# Trainii.net
KiCad netlist of a schematic drawn in EAGLE
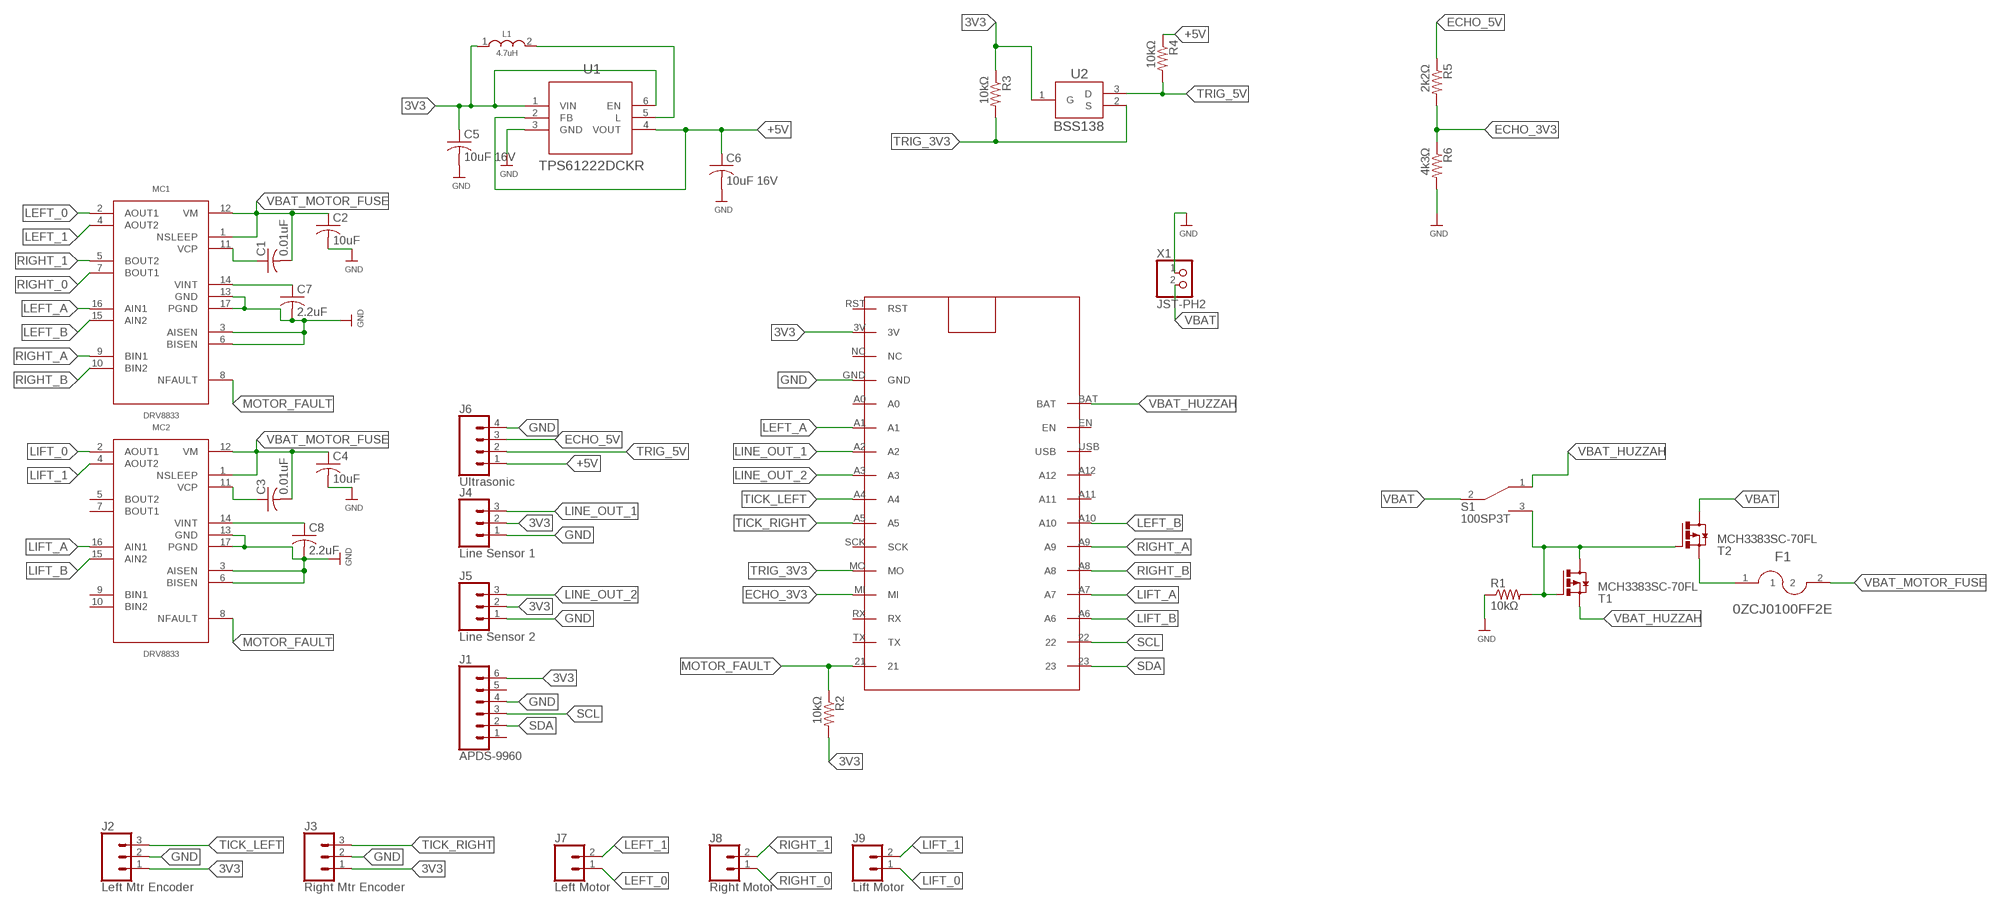
[diagram p0: schematic, sheet 1]

(export (version "E")
  (design (tool "Eeschema 10.0.6"))
  (components
    (comp (ref "C1")
      (value "0.01uF")
      (footprint "eagle-import:C0805")
      (libsource (lib "eagle-import") (part "C-USC0805"))
    )
    (comp (ref "C2")
      (value "10uF")
      (footprint "eagle-import:C0805")
      (libsource (lib "eagle-import") (part "C-USC0805"))
    )
    (comp (ref "C3")
      (value "0.01uF")
      (footprint "eagle-import:C0805")
      (libsource (lib "eagle-import") (part "C-USC0805"))
    )
    (comp (ref "C4")
      (value "10uF")
      (footprint "eagle-import:C0805")
      (libsource (lib "eagle-import") (part "C-USC0805"))
    )
    (comp (ref "C5")
      (value "10uF 16V")
      (footprint "eagle-import:C0805")
      (libsource (lib "eagle-import") (part "C-USC0805"))
    )
    (comp (ref "C6")
      (value "10uF 16V")
      (footprint "eagle-import:C0805")
      (libsource (lib "eagle-import") (part "C-USC0805"))
    )
    (comp (ref "C7")
      (value "2.2uF")
      (footprint "eagle-import:C0805")
      (libsource (lib "eagle-import") (part "C-USC0805"))
    )
    (comp (ref "C8")
      (value "2.2uF")
      (footprint "eagle-import:C0805")
      (libsource (lib "eagle-import") (part "C-USC0805"))
    )
    (comp (ref "F1")
      (value "0ZCJ0100FF2E")
      (footprint "eagle-import:1206")
      (libsource (lib "eagle-import") (part "0ZCJ0100FF2E"))
    )
    (comp (ref "J1")
      (value "APDS-9960")
      (footprint "eagle-import:1X06")
      (libsource (lib "eagle-import") (part "CONN_06SILK_FEMALE_PTH"))
    )
    (comp (ref "J2")
      (value "Left Mtr Encoder")
      (footprint "eagle-import:1X03")
      (libsource (lib "eagle-import") (part "CONN_03"))
    )
    (comp (ref "J3")
      (value "Right Mtr Encoder")
      (footprint "eagle-import:1X03")
      (libsource (lib "eagle-import") (part "CONN_03"))
    )
    (comp (ref "J4")
      (value "Line Sensor 1")
      (footprint "eagle-import:1X03")
      (libsource (lib "eagle-import") (part "CONN_03"))
    )
    (comp (ref "J5")
      (value "Line Sensor 2")
      (footprint "eagle-import:1X03")
      (libsource (lib "eagle-import") (part "CONN_03"))
    )
    (comp (ref "J6")
      (value "Ultrasonic")
      (footprint "eagle-import:1X04")
      (libsource (lib "eagle-import") (part "CONN_04"))
    )
    (comp (ref "J7")
      (value "Left Motor")
      (footprint "eagle-import:1X02")
      (libsource (lib "eagle-import") (part "CONN_02"))
    )
    (comp (ref "J8")
      (value "Right Motor")
      (footprint "eagle-import:1X02")
      (libsource (lib "eagle-import") (part "CONN_02"))
    )
    (comp (ref "J9")
      (value "Lift Motor")
      (footprint "eagle-import:1X02")
      (libsource (lib "eagle-import") (part "CONN_02"))
    )
    (comp (ref "L1")
      (value "4.7uH")
      (footprint "eagle-import:VLS3012HBX")
      (libsource (lib "eagle-import") (part "VLS3012HBX"))
    )
    (comp (ref "M1")
      (value "ESP32")
      (footprint "eagle-import:ESP32")
      (libsource (lib "eagle-import") (part "ESP32"))
    )
    (comp (ref "MC1")
      (value "DRV8833")
      (footprint "eagle-import:HTSSOP-16")
      (libsource (lib "eagle-import") (part "DRV8833"))
    )
    (comp (ref "MC2")
      (value "DRV8833")
      (footprint "eagle-import:HTSSOP-16")
      (libsource (lib "eagle-import") (part "DRV8833"))
    )
    (comp (ref "R1")
      (value "10kΩ")
      (footprint "eagle-import:R0805")
      (libsource (lib "eagle-import") (part "R-US_R0805"))
    )
    (comp (ref "R2")
      (value "10kΩ")
      (footprint "eagle-import:R0805")
      (libsource (lib "eagle-import") (part "R-US_R0805"))
    )
    (comp (ref "R3")
      (value "10kΩ")
      (footprint "eagle-import:R0805")
      (libsource (lib "eagle-import") (part "R-US_R0805"))
    )
    (comp (ref "R4")
      (value "10kΩ")
      (footprint "eagle-import:R0805")
      (libsource (lib "eagle-import") (part "R-US_R0805"))
    )
    (comp (ref "R5")
      (value "2k2Ω")
      (footprint "eagle-import:M0805")
      (libsource (lib "eagle-import") (part "R-US_M0805"))
    )
    (comp (ref "R6")
      (value "4k3Ω")
      (footprint "eagle-import:M0805")
      (libsource (lib "eagle-import") (part "R-US_M0805"))
    )
    (comp (ref "S1")
      (value "100SP3T")
      (footprint "eagle-import:100SP3T")
      (libsource (lib "eagle-import") (part "100SP3T"))
    )
    (comp (ref "T1")
      (value "MCH3383SC-70FL")
      (footprint "eagle-import:SOTFL65P210X90-3")
      (libsource (lib "eagle-import") (part "MCH3383SC-70FL"))
    )
    (comp (ref "T2")
      (value "MCH3383SC-70FL")
      (footprint "eagle-import:SOTFL65P210X90-3")
      (libsource (lib "eagle-import") (part "MCH3383SC-70FL"))
    )
    (comp (ref "U1")
      (value "TPS61222DCKR")
      (footprint "eagle-import:DCK6")
      (libsource (lib "eagle-import") (part "TPS61222DCKR"))
    )
    (comp (ref "U2")
      (value "BSS138")
      (footprint "eagle-import:SOT-23-3L")
      (libsource (lib "eagle-import") (part "BSS138"))
    )
    (comp (ref "X1")
      (value "JST-PH2")
      (footprint "eagle-import:JST-PH")
      (libsource (lib "eagle-import") (part "JST-PH2"))
    )
  )
  (nets
    (net (code "1") (name "+5V") (class "Default")
      (node (ref "C6") (pin "1") (pinfunction "1_1") (pintype "passive"))
      (node (ref "J6") (pin "1") (pinfunction "1_1") (pintype "passive"))
      (node (ref "R4") (pin "1") (pinfunction "1_1") (pintype "passive"))
      (node (ref "U1") (pin "2") (pinfunction "FB_2") (pintype "input"))
      (node (ref "U1") (pin "4") (pinfunction "VOUT_4") (pintype "output"))
    )
    (net (code "2") (name "3V3") (class "Default")
      (node (ref "C5") (pin "1") (pinfunction "1_1") (pintype "passive"))
      (node (ref "J1") (pin "6") (pinfunction "6_6") (pintype "passive"))
      (node (ref "J2") (pin "1") (pinfunction "1_1") (pintype "passive"))
      (node (ref "J3") (pin "1") (pinfunction "1_1") (pintype "passive"))
      (node (ref "J4") (pin "2") (pinfunction "2_2") (pintype "passive"))
      (node (ref "J5") (pin "2") (pinfunction "2_2") (pintype "passive"))
      (node (ref "L1") (pin "1") (pinfunction "IN_1") (pintype "passive"))
      (node (ref "M1") (pin "3V") (pinfunction "3V_3V") (pintype "bidirectional"))
      (node (ref "R2") (pin "2") (pinfunction "2_2") (pintype "passive"))
      (node (ref "R3") (pin "1") (pinfunction "1_1") (pintype "passive"))
      (node (ref "U1") (pin "1") (pinfunction "VIN_1") (pintype "input"))
      (node (ref "U1") (pin "6") (pinfunction "EN_6") (pintype "input"))
      (node (ref "U2") (pin "1") (pinfunction "G_1") (pintype "passive"))
    )
    (net (code "3") (name "ECHO_3V3") (class "Default")
      (node (ref "M1") (pin "MI") (pinfunction "MI_MI") (pintype "bidirectional"))
      (node (ref "R5") (pin "2") (pinfunction "2_2") (pintype "passive"))
      (node (ref "R6") (pin "1") (pinfunction "1_1") (pintype "passive"))
    )
    (net (code "4") (name "ECHO_5V") (class "Default")
      (node (ref "J6") (pin "3") (pinfunction "3_3") (pintype "passive"))
      (node (ref "R5") (pin "1") (pinfunction "1_1") (pintype "passive"))
    )
    (net (code "5") (name "GND") (class "Default")
      (node (ref "C2") (pin "2") (pinfunction "2_2") (pintype "passive"))
      (node (ref "C4") (pin "2") (pinfunction "2_2") (pintype "passive"))
      (node (ref "C5") (pin "2") (pinfunction "2_2") (pintype "passive"))
      (node (ref "C6") (pin "2") (pinfunction "2_2") (pintype "passive"))
      (node (ref "C7") (pin "2") (pinfunction "2_2") (pintype "passive"))
      (node (ref "C8") (pin "2") (pinfunction "2_2") (pintype "passive"))
      (node (ref "J1") (pin "4") (pinfunction "4_4") (pintype "passive"))
      (node (ref "J2") (pin "2") (pinfunction "2_2") (pintype "passive"))
      (node (ref "J3") (pin "2") (pinfunction "2_2") (pintype "passive"))
      (node (ref "J4") (pin "1") (pinfunction "1_1") (pintype "passive"))
      (node (ref "J5") (pin "1") (pinfunction "1_1") (pintype "passive"))
      (node (ref "J6") (pin "4") (pinfunction "4_4") (pintype "passive"))
      (node (ref "M1") (pin "GND") (pinfunction "GND_GND") (pintype "bidirectional"))
      (node (ref "MC1") (pin "13") (pinfunction "GND_13") (pintype "power_in"))
      (node (ref "MC1") (pin "17") (pinfunction "PGND_17") (pintype "power_in"))
      (node (ref "MC1") (pin "3") (pinfunction "AISEN_3") (pintype "bidirectional"))
      (node (ref "MC1") (pin "6") (pinfunction "BISEN_6") (pintype "bidirectional"))
      (node (ref "MC2") (pin "13") (pinfunction "GND_13") (pintype "power_in"))
      (node (ref "MC2") (pin "17") (pinfunction "PGND_17") (pintype "power_in"))
      (node (ref "MC2") (pin "3") (pinfunction "AISEN_3") (pintype "bidirectional"))
      (node (ref "MC2") (pin "6") (pinfunction "BISEN_6") (pintype "bidirectional"))
      (node (ref "R1") (pin "1") (pinfunction "1_1") (pintype "passive"))
      (node (ref "R6") (pin "2") (pinfunction "2_2") (pintype "passive"))
      (node (ref "U1") (pin "3") (pinfunction "GND_3") (pintype "power_in"))
      (node (ref "X1") (pin "1") (pinfunction "1_1") (pintype "passive"))
    )
    (net (code "6") (name "LEFT_0") (class "Default")
      (node (ref "J7") (pin "1") (pinfunction "1_1") (pintype "passive"))
      (node (ref "MC1") (pin "2") (pinfunction "AOUT1_2") (pintype "output"))
    )
    (net (code "7") (name "LEFT_1") (class "Default")
      (node (ref "J7") (pin "2") (pinfunction "2_2") (pintype "passive"))
      (node (ref "MC1") (pin "4") (pinfunction "AOUT2_4") (pintype "output"))
    )
    (net (code "8") (name "LEFT_A") (class "Default")
      (node (ref "M1") (pin "A1") (pinfunction "A1_A1") (pintype "bidirectional"))
      (node (ref "MC1") (pin "16") (pinfunction "AIN1_16") (pintype "input"))
    )
    (net (code "9") (name "LEFT_B") (class "Default")
      (node (ref "M1") (pin "A10") (pinfunction "A10_A10") (pintype "bidirectional"))
      (node (ref "MC1") (pin "15") (pinfunction "AIN2_15") (pintype "input"))
    )
    (net (code "10") (name "LIFT_0") (class "Default")
      (node (ref "J9") (pin "1") (pinfunction "1_1") (pintype "passive"))
      (node (ref "MC2") (pin "2") (pinfunction "AOUT1_2") (pintype "output"))
    )
    (net (code "11") (name "LIFT_1") (class "Default")
      (node (ref "J9") (pin "2") (pinfunction "2_2") (pintype "passive"))
      (node (ref "MC2") (pin "4") (pinfunction "AOUT2_4") (pintype "output"))
    )
    (net (code "12") (name "LIFT_A") (class "Default")
      (node (ref "M1") (pin "A7") (pinfunction "A7_A7") (pintype "bidirectional"))
      (node (ref "MC2") (pin "16") (pinfunction "AIN1_16") (pintype "input"))
    )
    (net (code "13") (name "LIFT_B") (class "Default")
      (node (ref "M1") (pin "A6") (pinfunction "A6_A6") (pintype "bidirectional"))
      (node (ref "MC2") (pin "15") (pinfunction "AIN2_15") (pintype "input"))
    )
    (net (code "14") (name "LINE_OUT_1") (class "Default")
      (node (ref "J4") (pin "3") (pinfunction "3_3") (pintype "passive"))
      (node (ref "M1") (pin "A2") (pinfunction "A2_A2") (pintype "bidirectional"))
    )
    (net (code "15") (name "LINE_OUT_2") (class "Default")
      (node (ref "J5") (pin "3") (pinfunction "3_3") (pintype "passive"))
      (node (ref "M1") (pin "A3") (pinfunction "A3_A3") (pintype "bidirectional"))
    )
    (net (code "16") (name "MOTOR_FAULT") (class "Default")
      (node (ref "M1") (pin "21") (pinfunction "21_21") (pintype "bidirectional"))
      (node (ref "MC1") (pin "8") (pinfunction "NFAULT_8") (pintype "output"))
      (node (ref "MC2") (pin "8") (pinfunction "NFAULT_8") (pintype "output"))
      (node (ref "R2") (pin "1") (pinfunction "1_1") (pintype "passive"))
    )
    (net (code "17") (name "Net-(L1-OUT)") (class "Default")
      (node (ref "L1") (pin "2") (pinfunction "OUT_2") (pintype "passive"))
      (node (ref "U1") (pin "5") (pinfunction "L_5") (pintype "input"))
    )
    (net (code "18") (name "Net-(MC1-VCP)") (class "Default")
      (node (ref "C1") (pin "1") (pinfunction "1_1") (pintype "passive"))
      (node (ref "MC1") (pin "11") (pinfunction "VCP_11") (pintype "bidirectional"))
    )
    (net (code "19") (name "Net-(MC1-VINT)") (class "Default")
      (node (ref "C7") (pin "1") (pinfunction "1_1") (pintype "passive"))
      (node (ref "MC1") (pin "14") (pinfunction "VINT_14") (pintype "power_in"))
    )
    (net (code "20") (name "Net-(MC2-VCP)") (class "Default")
      (node (ref "C3") (pin "1") (pinfunction "1_1") (pintype "passive"))
      (node (ref "MC2") (pin "11") (pinfunction "VCP_11") (pintype "bidirectional"))
    )
    (net (code "21") (name "Net-(MC2-VINT)") (class "Default")
      (node (ref "C8") (pin "1") (pinfunction "1_1") (pintype "passive"))
      (node (ref "MC2") (pin "14") (pinfunction "VINT_14") (pintype "power_in"))
    )
    (net (code "22") (name "Net-(S1-B)") (class "Default")
      (node (ref "R1") (pin "2") (pinfunction "2_2") (pintype "passive"))
      (node (ref "S1") (pin "3") (pinfunction "B_3") (pintype "bidirectional"))
      (node (ref "T1") (pin "1") (pinfunction "G_1") (pintype "passive"))
      (node (ref "T1") (pin "3") (pinfunction "D_3") (pintype "passive"))
      (node (ref "T2") (pin "1") (pinfunction "G_1") (pintype "passive"))
    )
    (net (code "23") (name "Net-(T2-S)") (class "Default")
      (node (ref "F1") (pin "1") (pinfunction "1_1") (pintype "passive"))
      (node (ref "T2") (pin "2") (pinfunction "S_2") (pintype "passive"))
    )
    (net (code "24") (name "RIGHT_0") (class "Default")
      (node (ref "J8") (pin "1") (pinfunction "1_1") (pintype "passive"))
      (node (ref "MC1") (pin "7") (pinfunction "BOUT1_7") (pintype "output"))
    )
    (net (code "25") (name "RIGHT_1") (class "Default")
      (node (ref "J8") (pin "2") (pinfunction "2_2") (pintype "passive"))
      (node (ref "MC1") (pin "5") (pinfunction "BOUT2_5") (pintype "output"))
    )
    (net (code "26") (name "RIGHT_A") (class "Default")
      (node (ref "M1") (pin "A9") (pinfunction "A9_A9") (pintype "bidirectional"))
      (node (ref "MC1") (pin "9") (pinfunction "BIN1_9") (pintype "input"))
    )
    (net (code "27") (name "RIGHT_B") (class "Default")
      (node (ref "M1") (pin "A8") (pinfunction "A8_A8") (pintype "bidirectional"))
      (node (ref "MC1") (pin "10") (pinfunction "BIN2_10") (pintype "input"))
    )
    (net (code "28") (name "SCL") (class "Default")
      (node (ref "J1") (pin "3") (pinfunction "3_3") (pintype "passive"))
      (node (ref "M1") (pin "22") (pinfunction "22_22") (pintype "bidirectional"))
    )
    (net (code "29") (name "SDA") (class "Default")
      (node (ref "J1") (pin "2") (pinfunction "2_2") (pintype "passive"))
      (node (ref "M1") (pin "23") (pinfunction "23_23") (pintype "bidirectional"))
    )
    (net (code "30") (name "TICK_LEFT") (class "Default")
      (node (ref "J2") (pin "3") (pinfunction "3_3") (pintype "passive"))
      (node (ref "M1") (pin "A4") (pinfunction "A4_A4") (pintype "bidirectional"))
    )
    (net (code "31") (name "TICK_RIGHT") (class "Default")
      (node (ref "J3") (pin "3") (pinfunction "3_3") (pintype "passive"))
      (node (ref "M1") (pin "A5") (pinfunction "A5_A5") (pintype "bidirectional"))
    )
    (net (code "32") (name "TRIG_3V3") (class "Default")
      (node (ref "M1") (pin "MO") (pinfunction "MO_MO") (pintype "bidirectional"))
      (node (ref "R3") (pin "2") (pinfunction "2_2") (pintype "passive"))
      (node (ref "U2") (pin "2") (pinfunction "S_2") (pintype "passive"))
    )
    (net (code "33") (name "TRIG_5V") (class "Default")
      (node (ref "J6") (pin "2") (pinfunction "2_2") (pintype "passive"))
      (node (ref "R4") (pin "2") (pinfunction "2_2") (pintype "passive"))
      (node (ref "U2") (pin "3") (pinfunction "D_3") (pintype "passive"))
    )
    (net (code "34") (name "VBAT") (class "Default")
      (node (ref "S1") (pin "2") (pinfunction "COMMON_2") (pintype "bidirectional"))
      (node (ref "T2") (pin "3") (pinfunction "D_3") (pintype "passive"))
      (node (ref "X1") (pin "2") (pinfunction "2_2") (pintype "passive"))
    )
    (net (code "35") (name "VBAT_HUZZAH") (class "Default")
      (node (ref "M1") (pin "BAT") (pinfunction "BAT_BAT") (pintype "bidirectional"))
      (node (ref "S1") (pin "1") (pinfunction "A_1") (pintype "bidirectional"))
      (node (ref "T1") (pin "2") (pinfunction "S_2") (pintype "passive"))
    )
    (net (code "36") (name "VBAT_MOTOR_FUSE") (class "Default")
      (node (ref "C1") (pin "2") (pinfunction "2_2") (pintype "passive"))
      (node (ref "C2") (pin "1") (pinfunction "1_1") (pintype "passive"))
      (node (ref "C3") (pin "2") (pinfunction "2_2") (pintype "passive"))
      (node (ref "C4") (pin "1") (pinfunction "1_1") (pintype "passive"))
      (node (ref "F1") (pin "2") (pinfunction "2_2") (pintype "passive"))
      (node (ref "MC1") (pin "1") (pinfunction "NSLEEP_1") (pintype "input"))
      (node (ref "MC1") (pin "12") (pinfunction "VM_12") (pintype "power_in"))
      (node (ref "MC2") (pin "1") (pinfunction "NSLEEP_1") (pintype "input"))
      (node (ref "MC2") (pin "12") (pinfunction "VM_12") (pintype "power_in"))
    )
    (net (code "37") (name "unconnected-(J1-Pad1)") (class "Default")
      (node (ref "J1") (pin "1") (pinfunction "1_1") (pintype "passive"))
    )
    (net (code "38") (name "unconnected-(J1-Pad5)") (class "Default")
      (node (ref "J1") (pin "5") (pinfunction "5_5") (pintype "passive"))
    )
    (net (code "39") (name "unconnected-(M1-PadA0)") (class "Default")
      (node (ref "M1") (pin "A0") (pinfunction "A0_A0") (pintype "bidirectional"))
    )
    (net (code "40") (name "unconnected-(M1-PadA11)") (class "Default")
      (node (ref "M1") (pin "A11") (pinfunction "A11_A11") (pintype "bidirectional"))
    )
    (net (code "41") (name "unconnected-(M1-PadA12)") (class "Default")
      (node (ref "M1") (pin "A12") (pinfunction "A12_A12") (pintype "bidirectional"))
    )
    (net (code "42") (name "unconnected-(M1-PadEN)") (class "Default")
      (node (ref "M1") (pin "EN") (pinfunction "EN_EN") (pintype "bidirectional"))
    )
    (net (code "43") (name "unconnected-(M1-PadNC)") (class "Default")
      (node (ref "M1") (pin "NC") (pinfunction "NC_NC") (pintype "bidirectional"))
    )
    (net (code "44") (name "unconnected-(M1-PadRST)") (class "Default")
      (node (ref "M1") (pin "RST") (pinfunction "RST_RST") (pintype "bidirectional"))
    )
    (net (code "45") (name "unconnected-(M1-PadRX)") (class "Default")
      (node (ref "M1") (pin "RX") (pinfunction "RX_RX") (pintype "bidirectional"))
    )
    (net (code "46") (name "unconnected-(M1-PadSCK)") (class "Default")
      (node (ref "M1") (pin "SCK") (pinfunction "SCK_SCK") (pintype "bidirectional"))
    )
    (net (code "47") (name "unconnected-(M1-PadTX)") (class "Default")
      (node (ref "M1") (pin "TX") (pinfunction "TX_TX") (pintype "bidirectional"))
    )
    (net (code "48") (name "unconnected-(M1-PadUSB)") (class "Default")
      (node (ref "M1") (pin "USB") (pinfunction "USB_USB") (pintype "bidirectional"))
    )
    (net (code "49") (name "unconnected-(MC2-BIN1-Pad9)") (class "Default")
      (node (ref "MC2") (pin "9") (pinfunction "BIN1_9") (pintype "input"))
    )
    (net (code "50") (name "unconnected-(MC2-BIN2-Pad10)") (class "Default")
      (node (ref "MC2") (pin "10") (pinfunction "BIN2_10") (pintype "input"))
    )
    (net (code "51") (name "unconnected-(MC2-BOUT1-Pad7)") (class "Default")
      (node (ref "MC2") (pin "7") (pinfunction "BOUT1_7") (pintype "output"))
    )
    (net (code "52") (name "unconnected-(MC2-BOUT2-Pad5)") (class "Default")
      (node (ref "MC2") (pin "5") (pinfunction "BOUT2_5") (pintype "output"))
    )
  )
)
